# choke_current_meas.net
KiCad netlist of a schematic drawn in Altium Designer
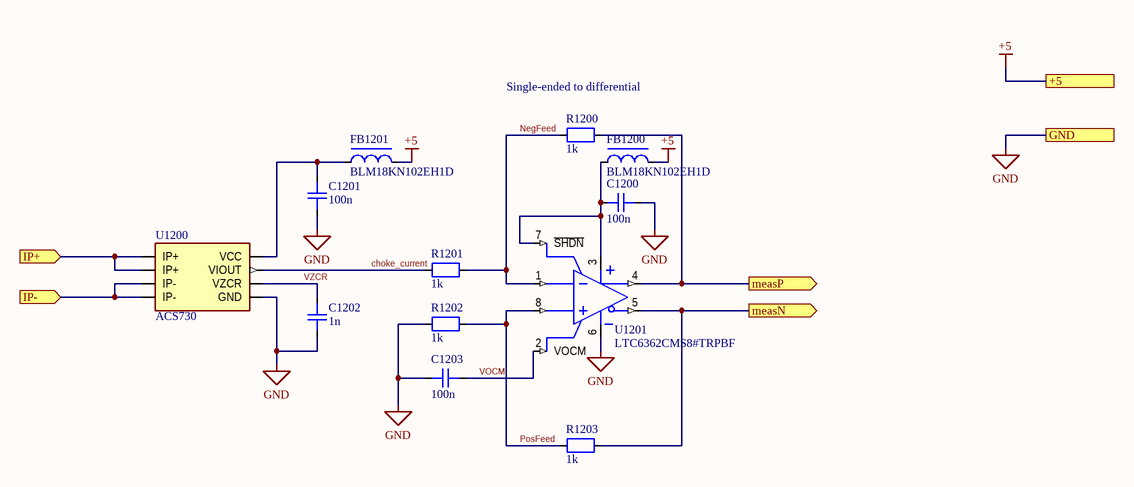
[diagram p0: choke_current_meas.SchDoc]

(export (version "E")
  (design (tool "Eeschema 10.0.6"))
  (components
    (comp (ref "C1200")
      (value "100n")
      (footprint "CAP0603")
      (libsource (lib "schematic_library") (part "Capacitor"))
    )
    (comp (ref "C1201")
      (value "100n")
      (footprint "CAP0603")
      (libsource (lib "schematic_library") (part "Capacitor"))
    )
    (comp (ref "C1202")
      (value "1n")
      (footprint "CAP0603")
      (libsource (lib "schematic_library") (part "Capacitor"))
    )
    (comp (ref "C1203")
      (value "100n")
      (footprint "CAP0603")
      (libsource (lib "schematic_library") (part "Capacitor"))
    )
    (comp (ref "FB1200")
      (value "BLM18KN102EH1D")
      (footprint "RES0603")
      (libsource (lib "schematic_library") (part "Ferrite Bead"))
    )
    (comp (ref "FB1201")
      (value "BLM18KN102EH1D")
      (footprint "RES0603")
      (libsource (lib "schematic_library") (part "Ferrite Bead"))
    )
    (comp (ref "R1200")
      (value "1k")
      (footprint "RES0603")
      (libsource (lib "schematic_library") (part "Resistor"))
    )
    (comp (ref "R1201")
      (value "1k")
      (footprint "RES0603")
      (libsource (lib "schematic_library") (part "Resistor"))
    )
    (comp (ref "R1202")
      (value "1k")
      (footprint "RES0603")
      (libsource (lib "schematic_library") (part "Resistor"))
    )
    (comp (ref "R1203")
      (value "1k")
      (footprint "RES0603")
      (libsource (lib "schematic_library") (part "Resistor"))
    )
    (comp (ref "U1200")
      (value "ACS730")
      (footprint "SOIC127P600X175-8N")
      (description "1 MHz Bandwidth, Galvanically Isolated Current Sensor IC in Small Footprint SOIC8 Package")
      (libsource (lib "schematic_library") (part "ACS730"))
    )
    (comp (ref "U1201")
      (value "LTC6362CMS8#TRPBF")
      (footprint "LT-MS8-8_M")
      (fields
        (field (name "LINEAR TECHNOLOGY PART NUMBER") "LTC6362")
        (field (name "MANUFACTURER") "Linear Technology")
      )
      (libsource (lib "schematic_library") (part "LTC6362"))
    )
  )
  (nets
    (net (code "1") (name "+5") (class "Default")
      (node (ref "FB1200") (pin "2") (pintype "passive"))
      (node (ref "FB1201") (pin "2") (pintype "passive"))
    )
    (net (code "2") (name "/IP+") (class "Default")
      (node (ref "U1200") (pin "1") (pinfunction "IP+_1") (pintype "passive"))
      (node (ref "U1200") (pin "2") (pinfunction "IP+_2") (pintype "passive"))
    )
    (net (code "3") (name "/IP-") (class "Default")
      (node (ref "U1200") (pin "3") (pinfunction "IP-_3") (pintype "passive"))
      (node (ref "U1200") (pin "4") (pinfunction "IP-_4") (pintype "passive"))
    )
    (net (code "4") (name "/NegFeed") (class "Default")
      (node (ref "R1200") (pin "2") (pintype "passive"))
      (node (ref "R1201") (pin "1") (pintype "passive"))
      (node (ref "U1201") (pin "1") (pinfunction "-IN_1") (pintype "input"))
    )
    (net (code "5") (name "/PosFeed") (class "Default")
      (node (ref "R1202") (pin "1") (pintype "passive"))
      (node (ref "R1203") (pin "2") (pintype "passive"))
      (node (ref "U1201") (pin "8") (pinfunction "+IN_8") (pintype "input"))
    )
    (net (code "6") (name "/VOCM") (class "Default")
      (node (ref "C1203") (pin "1") (pintype "passive"))
      (node (ref "U1201") (pin "2") (pinfunction "VOCM_2") (pintype "input"))
    )
    (net (code "7") (name "/VZCR") (class "Default")
      (node (ref "C1202") (pin "2") (pintype "passive"))
      (node (ref "U1200") (pin "6") (pinfunction "VZCR_6") (pintype "passive"))
    )
    (net (code "8") (name "/choke_current") (class "Default")
      (node (ref "R1201") (pin "2") (pintype "passive"))
      (node (ref "U1200") (pin "7") (pinfunction "VIOUT_7") (pintype "output"))
    )
    (net (code "9") (name "/measN") (class "Default")
      (node (ref "R1203") (pin "1") (pintype "passive"))
      (node (ref "U1201") (pin "5") (pinfunction "-OUT_5") (pintype "output"))
    )
    (net (code "10") (name "/measP") (class "Default")
      (node (ref "R1200") (pin "1") (pintype "passive"))
      (node (ref "U1201") (pin "4") (pinfunction "+OUT_4") (pintype "output"))
    )
    (net (code "11") (name "GND") (class "Default")
      (node (ref "C1200") (pin "1") (pintype "passive"))
      (node (ref "C1201") (pin "1") (pintype "passive"))
      (node (ref "C1202") (pin "1") (pintype "passive"))
      (node (ref "C1203") (pin "2") (pintype "passive"))
      (node (ref "R1202") (pin "2") (pintype "passive"))
      (node (ref "U1200") (pin "5") (pinfunction "GND_5") (pintype "power_in"))
      (node (ref "U1201") (pin "6") (pinfunction "V-_6") (pintype "power_in"))
    )
    (net (code "12") (name "Net-(U1200-VCC)") (class "Default")
      (node (ref "C1201") (pin "2") (pintype "passive"))
      (node (ref "FB1201") (pin "1") (pintype "passive"))
      (node (ref "U1200") (pin "8") (pinfunction "VCC_8") (pintype "power_in"))
    )
    (net (code "13") (name "Net-(U1201-V+)") (class "Default")
      (node (ref "C1200") (pin "2") (pintype "passive"))
      (node (ref "FB1200") (pin "1") (pintype "passive"))
      (node (ref "U1201") (pin "3") (pinfunction "V+_3") (pintype "power_in"))
      (node (ref "U1201") (pin "7") (pinfunction "~{SHDN}_7") (pintype "input"))
    )
  )
)
